# Main_Board_Germany_2016.net
KiCad netlist of a schematic drawn in EAGLE
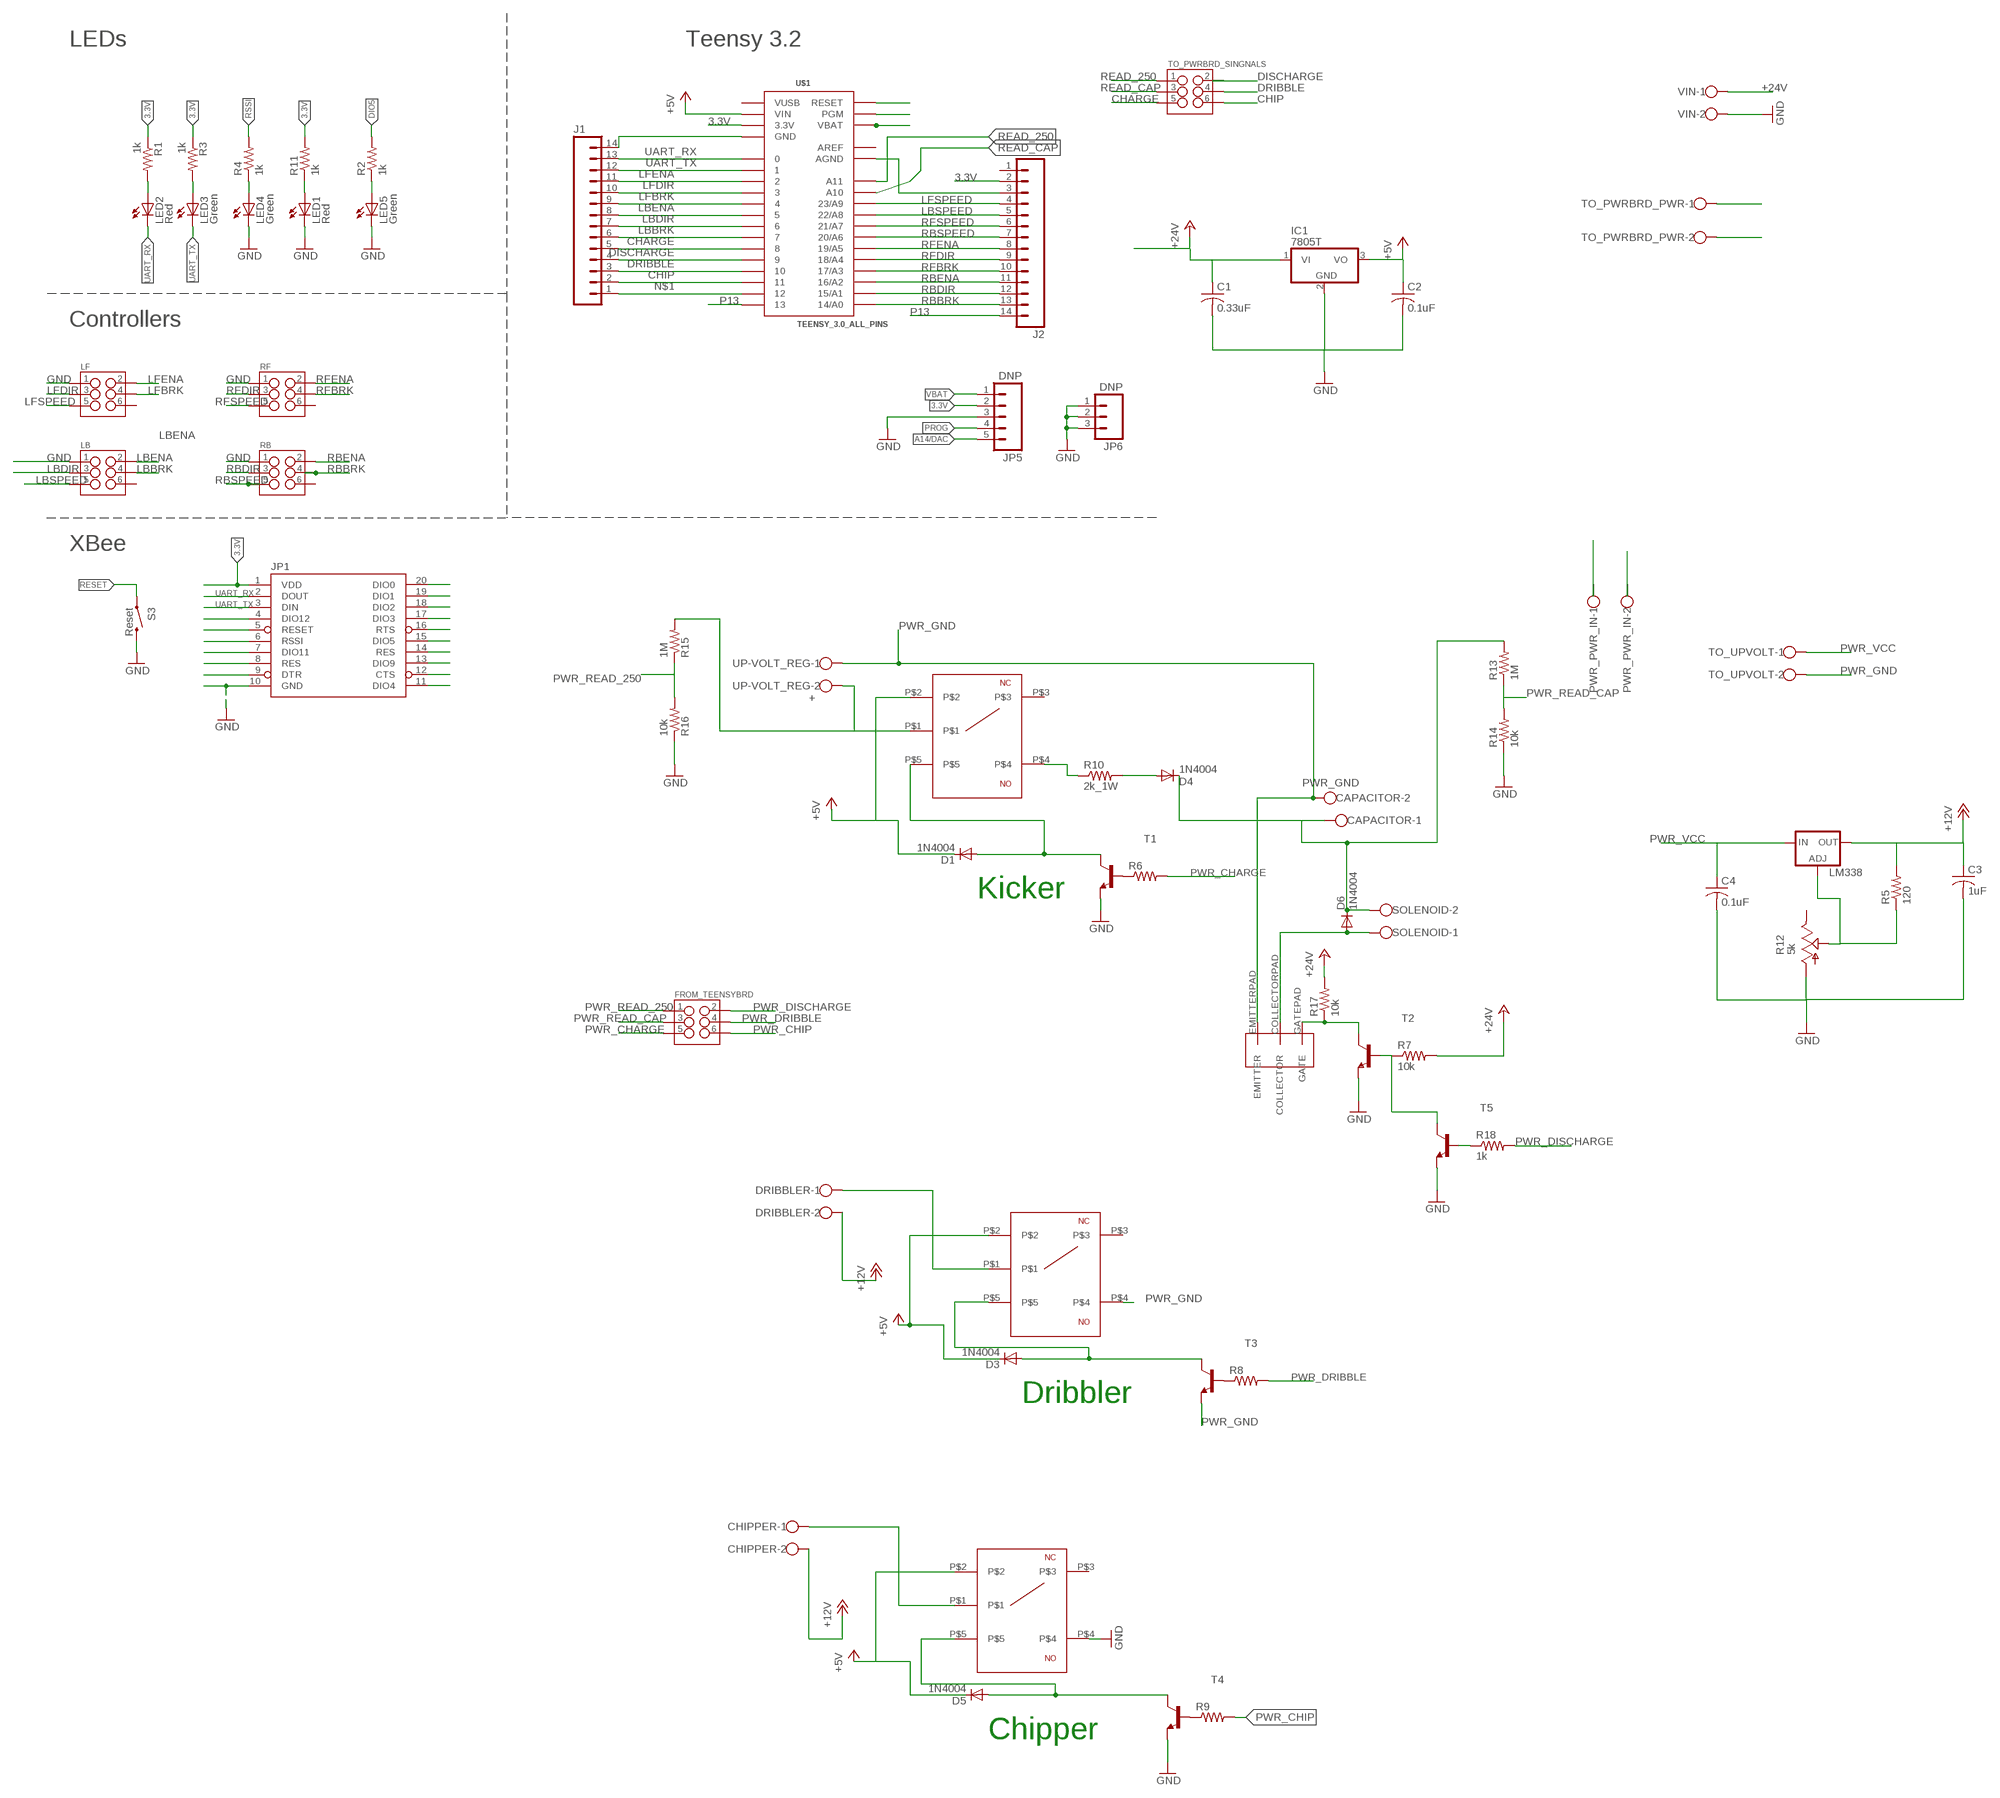
[diagram p0: schematic, sheet 1]

(export (version "E")
  (design (tool "Eeschema 10.0.6"))
  (components
    (comp (ref "C1")
      (value "0.33uF")
      (footprint "eagle-import:C0805")
      (libsource (lib "eagle-import") (part "C-USC0805"))
    )
    (comp (ref "C2")
      (value "0.1uF")
      (footprint "eagle-import:C0805")
      (libsource (lib "eagle-import") (part "C-USC0805"))
    )
    (comp (ref "C3")
      (value "1uF")
      (footprint "eagle-import:C0805")
      (libsource (lib "eagle-import") (part "C-USC0805"))
    )
    (comp (ref "C4")
      (value "0.1uF")
      (footprint "eagle-import:C0805")
      (libsource (lib "eagle-import") (part "C-USC0805"))
    )
    (comp (ref "CAPACITOR")
      (value "W237-102")
      (footprint "eagle-import:W237-102")
      (fields (field (name "MPN") "237-102"))
      (libsource (lib "eagle-import") (part "W237-102"))
    )
    (comp (ref "CHIPPER")
      (value "W237-102")
      (footprint "eagle-import:W237-102")
      (fields (field (name "MPN") "237-102"))
      (libsource (lib "eagle-import") (part "W237-102"))
    )
    (comp (ref "D1")
      (value "1N4004")
      (footprint "eagle-import:DO41-10")
      (libsource (lib "eagle-import") (part "1N4004"))
    )
    (comp (ref "D3")
      (value "1N4004")
      (footprint "eagle-import:DO41-10")
      (libsource (lib "eagle-import") (part "1N4004"))
    )
    (comp (ref "D4")
      (value "1N4004")
      (footprint "eagle-import:DO41-10")
      (libsource (lib "eagle-import") (part "1N4004"))
    )
    (comp (ref "D5")
      (value "1N4004")
      (footprint "eagle-import:DO41-10")
      (libsource (lib "eagle-import") (part "1N4004"))
    )
    (comp (ref "D6")
      (value "1N4004")
      (footprint "eagle-import:DO41-10")
      (libsource (lib "eagle-import") (part "1N4004"))
    )
    (comp (ref "DRIBBLER")
      (value "W237-102")
      (footprint "eagle-import:W237-102")
      (fields (field (name "MPN") "237-102"))
      (libsource (lib "eagle-import") (part "W237-102"))
    )
    (comp (ref "FROM_TEENSYBRD")
      (value "M03X2POGO_PINS")
      (footprint "eagle-import:2X3_POGO")
      (libsource (lib "eagle-import") (part "M03X2POGO_PINS"))
    )
    (comp (ref "IC1")
      (value "7805T")
      (footprint "eagle-import:TO220H")
      (libsource (lib "eagle-import") (part "78T05"))
    )
    (comp (ref "J1")
      (value "M14")
      (footprint "eagle-import:1X14")
      (libsource (lib "eagle-import") (part "M14"))
    )
    (comp (ref "J2")
      (value "M14")
      (footprint "eagle-import:1X14")
      (libsource (lib "eagle-import") (part "M14"))
    )
    (comp (ref "JP1")
      (value "XBEE-1B1")
      (footprint "eagle-import:XBEE-1")
      (libsource (lib "eagle-import") (part "XBEE-1B1"))
    )
    (comp (ref "JP5")
      (value "DNP")
      (footprint "eagle-import:1X05")
      (libsource (lib "eagle-import") (part "M05PTH"))
    )
    (comp (ref "JP6")
      (value "DNP")
      (footprint "eagle-import:1X03")
      (libsource (lib "eagle-import") (part "M03PTH"))
    )
    (comp (ref "LB")
      (value "M03X2POGO_PINS")
      (footprint "eagle-import:2X3_POGO")
      (libsource (lib "eagle-import") (part "M03X2POGO_PINS"))
    )
    (comp (ref "LED1")
      (value "Red")
      (footprint "eagle-import:LED-0603")
      (libsource (lib "eagle-import") (part "LED-RED0603"))
    )
    (comp (ref "LED2")
      (value "Red")
      (footprint "eagle-import:LED-0603")
      (libsource (lib "eagle-import") (part "LED-RED0603"))
    )
    (comp (ref "LED3")
      (value "Green")
      (footprint "eagle-import:LED-0603")
      (libsource (lib "eagle-import") (part "LED-GREEN0603"))
    )
    (comp (ref "LED4")
      (value "Green")
      (footprint "eagle-import:LED-0603")
      (libsource (lib "eagle-import") (part "LED-GREEN0603"))
    )
    (comp (ref "LED5")
      (value "Green")
      (footprint "eagle-import:LED-0603")
      (libsource (lib "eagle-import") (part "LED-GREEN0603"))
    )
    (comp (ref "LF")
      (value "M03X2POGO_PINS")
      (footprint "eagle-import:2X3_POGO")
      (libsource (lib "eagle-import") (part "M03X2POGO_PINS"))
    )
    (comp (ref "LM338")
      (value "LM317TL")
      (footprint "eagle-import:317TL")
      (libsource (lib "eagle-import") (part "LM317TL"))
    )
    (comp (ref "PWR_PWR_IN")
      (value "W237-102")
      (footprint "eagle-import:W237-102")
      (fields (field (name "MPN") "237-102"))
      (libsource (lib "eagle-import") (part "W237-102"))
    )
    (comp (ref "R1")
      (value "1k")
      (footprint "eagle-import:0603-RES")
      (libsource (lib "eagle-import") (part "1KOHM1/10W1%(0603)"))
    )
    (comp (ref "R2")
      (value "1k")
      (footprint "eagle-import:0603-RES")
      (libsource (lib "eagle-import") (part "1KOHM1/10W1%(0603)"))
    )
    (comp (ref "R3")
      (value "1k")
      (footprint "eagle-import:0603-RES")
      (libsource (lib "eagle-import") (part "1KOHM1/10W1%(0603)"))
    )
    (comp (ref "R4")
      (value "1k")
      (footprint "eagle-import:0603-RES")
      (libsource (lib "eagle-import") (part "1KOHM1/10W1%(0603)"))
    )
    (comp (ref "R5")
      (value "120")
      (footprint "eagle-import:M0805")
      (libsource (lib "eagle-import") (part "R-US_M0805"))
    )
    (comp (ref "R6")
      (value "R-US_0207/7")
      (footprint "eagle-import:0207_7")
      (libsource (lib "eagle-import") (part "R-US_0207/7"))
    )
    (comp (ref "R7")
      (value "10k")
      (footprint "eagle-import:0207_7")
      (libsource (lib "eagle-import") (part "R-US_0207/7"))
    )
    (comp (ref "R8")
      (value "R-US_0207/7")
      (footprint "eagle-import:0207_7")
      (libsource (lib "eagle-import") (part "R-US_0207/7"))
    )
    (comp (ref "R9")
      (value "R-US_0207/7")
      (footprint "eagle-import:0207_7")
      (libsource (lib "eagle-import") (part "R-US_0207/7"))
    )
    (comp (ref "R10")
      (value "2k_1W")
      (footprint "eagle-import:0309_12")
      (libsource (lib "eagle-import") (part "R-US_0309/12"))
    )
    (comp (ref "R11")
      (value "1k")
      (footprint "eagle-import:0603-RES")
      (libsource (lib "eagle-import") (part "1KOHM1/10W1%(0603)"))
    )
    (comp (ref "R12")
      (value "5k")
      (footprint "eagle-import:B25P")
      (libsource (lib "eagle-import") (part "TRIM_US-B25P"))
    )
    (comp (ref "R13")
      (value "1M")
      (footprint "eagle-import:M0805")
      (libsource (lib "eagle-import") (part "R-US_M0805"))
    )
    (comp (ref "R14")
      (value "10k")
      (footprint "eagle-import:M0805")
      (libsource (lib "eagle-import") (part "R-US_M0805"))
    )
    (comp (ref "R15")
      (value "1M")
      (footprint "eagle-import:M0805")
      (libsource (lib "eagle-import") (part "R-US_M0805"))
    )
    (comp (ref "R16")
      (value "10k")
      (footprint "eagle-import:M0805")
      (libsource (lib "eagle-import") (part "R-US_M0805"))
    )
    (comp (ref "R17")
      (value "10k")
      (footprint "eagle-import:0207_7")
      (libsource (lib "eagle-import") (part "R-US_0207/7"))
    )
    (comp (ref "R18")
      (value "1k")
      (footprint "eagle-import:0207_7")
      (libsource (lib "eagle-import") (part "R-US_0207/7"))
    )
    (comp (ref "RB")
      (value "M03X2POGO_PINS")
      (footprint "eagle-import:2X3_POGO")
      (libsource (lib "eagle-import") (part "M03X2POGO_PINS"))
    )
    (comp (ref "RF")
      (value "M03X2POGO_PINS")
      (footprint "eagle-import:2X3_POGO")
      (libsource (lib "eagle-import") (part "M03X2POGO_PINS"))
    )
    (comp (ref "S3")
      (value "Reset")
      (footprint "eagle-import:TACTILE-SWITCH-SMD")
      (libsource (lib "eagle-import") (part "SWITCH-MOMENTARY-2SMD"))
    )
    (comp (ref "SOLENOID")
      (value "W237-102")
      (footprint "eagle-import:W237-102")
      (fields (field (name "MPN") "237-102"))
      (libsource (lib "eagle-import") (part "W237-102"))
    )
    (comp (ref "T1")
      (value "2N3904-NPN-TO92-EBC")
      (footprint "eagle-import:TO92-EBC")
      (libsource (lib "eagle-import") (part "-NPN-TO92-EBC2N3904"))
    )
    (comp (ref "T2")
      (value "2N3904-NPN-TO92-EBC")
      (footprint "eagle-import:TO92-EBC")
      (libsource (lib "eagle-import") (part "-NPN-TO92-EBC2N3904"))
    )
    (comp (ref "T3")
      (value "2N3904-NPN-TO92-EBC")
      (footprint "eagle-import:TO92-EBC")
      (libsource (lib "eagle-import") (part "-NPN-TO92-EBC2N3904"))
    )
    (comp (ref "T4")
      (value "2N3904-NPN-TO92-EBC")
      (footprint "eagle-import:TO92-EBC")
      (libsource (lib "eagle-import") (part "-NPN-TO92-EBC2N3904"))
    )
    (comp (ref "T5")
      (value "2N3904-NPN-TO92-EBC")
      (footprint "eagle-import:TO92-EBC")
      (libsource (lib "eagle-import") (part "-NPN-TO92-EBC2N3904"))
    )
    (comp (ref "TO_PWRBRD_PWR")
      (value "W237-102")
      (footprint "eagle-import:W237-102")
      (fields (field (name "MPN") "237-102"))
      (libsource (lib "eagle-import") (part "W237-102"))
    )
    (comp (ref "TO_PWRBRD_SINGNALS")
      (value "M03X2POGO_PINS")
      (footprint "eagle-import:2X3_POGO")
      (libsource (lib "eagle-import") (part "M03X2POGO_PINS"))
    )
    (comp (ref "TO_UPVOLT")
      (value "W237-102")
      (footprint "eagle-import:W237-102")
      (fields (field (name "MPN") "237-102"))
      (libsource (lib "eagle-import") (part "W237-102"))
    )
    (comp (ref "U$1")
      (value "TEENSY_3.0_ALL_PINS")
      (footprint "eagle-import:TEENSY3-ALL_PINS")
      (libsource (lib "eagle-import") (part "TEENSY_3.0_ALL_PINS"))
    )
    (comp (ref "U$2")
      (value "APT75GN120LG")
      (footprint "eagle-import:TO-264")
      (libsource (lib "eagle-import") (part "APT75GN120LG"))
    )
    (comp (ref "U$3")
      (value "PANASONIC_JS1")
      (footprint "eagle-import:PANASONIC_JS1")
      (libsource (lib "eagle-import") (part "PANASONIC_JS1"))
    )
    (comp (ref "U$4")
      (value "PANASONIC_JS1")
      (footprint "eagle-import:PANASONIC_JS1")
      (libsource (lib "eagle-import") (part "PANASONIC_JS1"))
    )
    (comp (ref "U$5")
      (value "PANASONIC_JS1")
      (footprint "eagle-import:PANASONIC_JS1")
      (libsource (lib "eagle-import") (part "PANASONIC_JS1"))
    )
    (comp (ref "UP-VOLT_REG")
      (value "+")
      (footprint "eagle-import:W237-102")
      (fields (field (name "MPN") "237-102"))
      (libsource (lib "eagle-import") (part "W237-102"))
    )
    (comp (ref "VIN")
      (value "W237-102")
      (footprint "eagle-import:W237-102")
      (fields (field (name "MPN") "237-102"))
      (libsource (lib "eagle-import") (part "W237-102"))
    )
  )
  (nets
    (net (code "1") (name "+5V") (class "Default")
      (node (ref "C2") (pin "1") (pinfunction "1_1") (pintype "passive"))
      (node (ref "D1") (pin "C") (pinfunction "C_C") (pintype "passive"))
      (node (ref "D3") (pin "C") (pinfunction "C_C") (pintype "passive"))
      (node (ref "D5") (pin "C") (pinfunction "C_C") (pintype "passive"))
      (node (ref "IC1") (pin "3") (pinfunction "VO_3") (pintype "passive"))
      (node (ref "U$1") (pin "VIN") (pinfunction "VIN_VIN") (pintype "power_in"))
      (node (ref "U$3") (pin "P$2") (pinfunction "P$2_P$2") (pintype "bidirectional"))
      (node (ref "U$4") (pin "P$2") (pinfunction "P$2_P$2") (pintype "bidirectional"))
      (node (ref "U$5") (pin "P$2") (pinfunction "P$2_P$2") (pintype "bidirectional"))
    )
    (net (code "2") (name "+12V") (class "Default")
      (node (ref "C3") (pin "1") (pinfunction "1_1") (pintype "passive"))
      (node (ref "CHIPPER") (pin "2") (pinfunction "KL_2") (pintype "passive"))
      (node (ref "DRIBBLER") (pin "2") (pinfunction "KL_2") (pintype "passive"))
      (node (ref "LM338") (pin "2") (pinfunction "OUT_2") (pintype "passive"))
      (node (ref "R5") (pin "2") (pinfunction "2_2") (pintype "passive"))
    )
    (net (code "3") (name "+24V") (class "Default")
      (node (ref "C1") (pin "1") (pinfunction "1_1") (pintype "passive"))
      (node (ref "IC1") (pin "1") (pinfunction "VI_1") (pintype "input"))
      (node (ref "R17") (pin "2") (pinfunction "2_2") (pintype "passive"))
      (node (ref "R7") (pin "2") (pinfunction "2_2") (pintype "passive"))
      (node (ref "TO_PWRBRD_PWR") (pin "1") (pinfunction "KL_1") (pintype "passive"))
      (node (ref "VIN") (pin "1") (pinfunction "KL_1") (pintype "passive"))
    )
    (net (code "4") (name "/AREF") (class "Default")
      (node (ref "U$1") (pin "AREF") (pinfunction "AREF_AREF") (pintype "power_in"))
    )
    (net (code "5") (name "/CHARGE") (class "Default")
      (node (ref "J1") (pin "5") (pinfunction "5_5") (pintype "passive"))
      (node (ref "TO_PWRBRD_SINGNALS") (pin "P$5") (pinfunction "5_P$5") (pintype "bidirectional"))
      (node (ref "U$1") (pin "8") (pinfunction "8_8") (pintype "bidirectional"))
    )
    (net (code "6") (name "/CHIP") (class "Default")
      (node (ref "J1") (pin "2") (pinfunction "2_2") (pintype "passive"))
      (node (ref "TO_PWRBRD_SINGNALS") (pin "P$6") (pinfunction "6_P$6") (pintype "bidirectional"))
      (node (ref "U$1") (pin "11") (pinfunction "11_11") (pintype "bidirectional"))
    )
    (net (code "7") (name "/DISCHARGE") (class "Default")
      (node (ref "J1") (pin "4") (pinfunction "4_4") (pintype "passive"))
      (node (ref "U$1") (pin "9") (pinfunction "9_9") (pintype "bidirectional"))
    )
    (net (code "8") (name "/DRIBBLE") (class "Default")
      (node (ref "J1") (pin "3") (pinfunction "3_3") (pintype "passive"))
      (node (ref "TO_PWRBRD_SINGNALS") (pin "P$4") (pinfunction "4_P$4") (pintype "bidirectional"))
      (node (ref "U$1") (pin "10") (pinfunction "10_10") (pintype "bidirectional"))
    )
    (net (code "9") (name "/LBBRK") (class "Default")
      (node (ref "J1") (pin "6") (pinfunction "6_6") (pintype "passive"))
      (node (ref "LB") (pin "P$4") (pinfunction "4_P$4") (pintype "bidirectional"))
      (node (ref "U$1") (pin "7") (pinfunction "7_7") (pintype "bidirectional"))
    )
    (net (code "10") (name "/LBDIR") (class "Default")
      (node (ref "J1") (pin "7") (pinfunction "7_7") (pintype "passive"))
      (node (ref "LB") (pin "P$3") (pinfunction "3_P$3") (pintype "bidirectional"))
      (node (ref "U$1") (pin "6") (pinfunction "6_6") (pintype "bidirectional"))
    )
    (net (code "11") (name "/LBENA") (class "Default")
      (node (ref "J1") (pin "8") (pinfunction "8_8") (pintype "passive"))
      (node (ref "LB") (pin "P$2") (pinfunction "2_P$2") (pintype "bidirectional"))
      (node (ref "U$1") (pin "5") (pinfunction "5_5") (pintype "bidirectional"))
    )
    (net (code "12") (name "/LBSPEED") (class "Default")
      (node (ref "J2") (pin "5") (pinfunction "5_5") (pintype "passive"))
      (node (ref "LB") (pin "P$5") (pinfunction "5_P$5") (pintype "bidirectional"))
      (node (ref "U$1") (pin "22/A8") (pinfunction "22/A8_22/A8") (pintype "bidirectional"))
    )
    (net (code "13") (name "/LFBRK") (class "Default")
      (node (ref "J1") (pin "9") (pinfunction "9_9") (pintype "passive"))
      (node (ref "LF") (pin "P$4") (pinfunction "4_P$4") (pintype "bidirectional"))
      (node (ref "U$1") (pin "4") (pinfunction "4_4") (pintype "bidirectional"))
    )
    (net (code "14") (name "/LFDIR") (class "Default")
      (node (ref "J1") (pin "10") (pinfunction "10_10") (pintype "passive"))
      (node (ref "LF") (pin "P$3") (pinfunction "3_P$3") (pintype "bidirectional"))
      (node (ref "U$1") (pin "3") (pinfunction "3_3") (pintype "bidirectional"))
    )
    (net (code "15") (name "/LFENA") (class "Default")
      (node (ref "J1") (pin "11") (pinfunction "11_11") (pintype "passive"))
      (node (ref "LF") (pin "P$2") (pinfunction "2_P$2") (pintype "bidirectional"))
      (node (ref "U$1") (pin "2") (pinfunction "2_2") (pintype "bidirectional"))
    )
    (net (code "16") (name "/LFSPEED") (class "Default")
      (node (ref "J2") (pin "4") (pinfunction "4_4") (pintype "passive"))
      (node (ref "LF") (pin "P$5") (pinfunction "5_P$5") (pintype "bidirectional"))
      (node (ref "U$1") (pin "23/A9") (pinfunction "23/A9_23/A9") (pintype "bidirectional"))
    )
    (net (code "17") (name "/N$1") (class "Default")
      (node (ref "J1") (pin "1") (pinfunction "1_1") (pintype "passive"))
      (node (ref "U$1") (pin "12") (pinfunction "12_12") (pintype "bidirectional"))
    )
    (net (code "18") (name "/P13") (class "Default")
      (node (ref "J2") (pin "14") (pinfunction "14_14") (pintype "passive"))
      (node (ref "U$1") (pin "13") (pinfunction "13_13") (pintype "bidirectional"))
    )
    (net (code "19") (name "/PWR_CHARGE") (class "Default")
      (node (ref "FROM_TEENSYBRD") (pin "P$5") (pinfunction "5_P$5") (pintype "bidirectional"))
      (node (ref "R6") (pin "2") (pinfunction "2_2") (pintype "passive"))
    )
    (net (code "20") (name "/PWR_DISCHARGE") (class "Default")
      (node (ref "FROM_TEENSYBRD") (pin "P$2") (pinfunction "2_P$2") (pintype "bidirectional"))
      (node (ref "R18") (pin "2") (pinfunction "2_2") (pintype "passive"))
    )
    (net (code "21") (name "/PWR_DRIBBLE") (class "Default")
      (node (ref "FROM_TEENSYBRD") (pin "P$4") (pinfunction "4_P$4") (pintype "bidirectional"))
      (node (ref "R8") (pin "2") (pinfunction "2_2") (pintype "passive"))
    )
    (net (code "22") (name "/PWR_GND") (class "Default")
      (node (ref "CAPACITOR") (pin "2") (pinfunction "KL_2") (pintype "passive"))
      (node (ref "T3") (pin "E") (pinfunction "E_E") (pintype "passive"))
      (node (ref "TO_UPVOLT") (pin "2") (pinfunction "KL_2") (pintype "passive"))
      (node (ref "U$2") (pin "EMITTERPAD") (pinfunction "EMITTER_EMITTERPAD") (pintype "bidirectional"))
      (node (ref "U$4") (pin "P$4") (pinfunction "P$4_P$4") (pintype "bidirectional"))
      (node (ref "UP-VOLT_REG") (pin "1") (pinfunction "KL_1") (pintype "passive"))
    )
    (net (code "23") (name "/PWR_READ_250") (class "Default")
      (node (ref "FROM_TEENSYBRD") (pin "P$1") (pinfunction "1_P$1") (pintype "bidirectional"))
      (node (ref "R15") (pin "1") (pinfunction "1_1") (pintype "passive"))
      (node (ref "R16") (pin "2") (pinfunction "2_2") (pintype "passive"))
    )
    (net (code "24") (name "/PWR_READ_CAP") (class "Default")
      (node (ref "FROM_TEENSYBRD") (pin "P$3") (pinfunction "3_P$3") (pintype "bidirectional"))
      (node (ref "R13") (pin "1") (pinfunction "1_1") (pintype "passive"))
      (node (ref "R14") (pin "2") (pinfunction "2_2") (pintype "passive"))
    )
    (net (code "25") (name "/PWR_VCC") (class "Default")
      (node (ref "C4") (pin "1") (pinfunction "1_1") (pintype "passive"))
      (node (ref "LM338") (pin "3") (pinfunction "IN_3") (pintype "input"))
      (node (ref "TO_UPVOLT") (pin "1") (pinfunction "KL_1") (pintype "passive"))
    )
    (net (code "26") (name "/RBBRK") (class "Default")
      (node (ref "J2") (pin "13") (pinfunction "13_13") (pintype "passive"))
      (node (ref "RB") (pin "P$4") (pinfunction "4_P$4") (pintype "bidirectional"))
      (node (ref "U$1") (pin "14/A0") (pinfunction "14/A0_14/A0") (pintype "bidirectional"))
    )
    (net (code "27") (name "/RBDIR") (class "Default")
      (node (ref "J2") (pin "12") (pinfunction "12_12") (pintype "passive"))
      (node (ref "RB") (pin "P$3") (pinfunction "3_P$3") (pintype "bidirectional"))
      (node (ref "U$1") (pin "15/A1") (pinfunction "15/A1_15/A1") (pintype "bidirectional"))
    )
    (net (code "28") (name "/RBENA") (class "Default")
      (node (ref "J2") (pin "11") (pinfunction "11_11") (pintype "passive"))
      (node (ref "RB") (pin "P$2") (pinfunction "2_P$2") (pintype "bidirectional"))
      (node (ref "U$1") (pin "16/A2") (pinfunction "16/A2_16/A2") (pintype "bidirectional"))
    )
    (net (code "29") (name "/RBSPEED") (class "Default")
      (node (ref "J2") (pin "7") (pinfunction "7_7") (pintype "passive"))
      (node (ref "RB") (pin "P$5") (pinfunction "5_P$5") (pintype "bidirectional"))
      (node (ref "U$1") (pin "20/A6") (pinfunction "20/A6_20/A6") (pintype "bidirectional"))
    )
    (net (code "30") (name "/RFBRK") (class "Default")
      (node (ref "J2") (pin "10") (pinfunction "10_10") (pintype "passive"))
      (node (ref "RF") (pin "P$4") (pinfunction "4_P$4") (pintype "bidirectional"))
      (node (ref "U$1") (pin "17/A3") (pinfunction "17/A3_17/A3") (pintype "bidirectional"))
    )
    (net (code "31") (name "/RFDIR") (class "Default")
      (node (ref "J2") (pin "9") (pinfunction "9_9") (pintype "passive"))
      (node (ref "RF") (pin "P$3") (pinfunction "3_P$3") (pintype "bidirectional"))
      (node (ref "U$1") (pin "18/A4") (pinfunction "18/A4_18/A4") (pintype "bidirectional"))
    )
    (net (code "32") (name "/RFENA") (class "Default")
      (node (ref "J2") (pin "8") (pinfunction "8_8") (pintype "passive"))
      (node (ref "RF") (pin "P$2") (pinfunction "2_P$2") (pintype "bidirectional"))
      (node (ref "U$1") (pin "19/A5") (pinfunction "19/A5_19/A5") (pintype "bidirectional"))
    )
    (net (code "33") (name "/RFSPEED") (class "Default")
      (node (ref "J2") (pin "6") (pinfunction "6_6") (pintype "passive"))
      (node (ref "RF") (pin "P$5") (pinfunction "5_P$5") (pintype "bidirectional"))
      (node (ref "U$1") (pin "21/A7") (pinfunction "21/A7_21/A7") (pintype "bidirectional"))
    )
    (net (code "34") (name "/VUSB") (class "Default")
      (node (ref "U$1") (pin "VUSB") (pinfunction "VUSB_VUSB") (pintype "power_in"))
    )
    (net (code "35") (name "3.3V") (class "Default")
      (node (ref "J2") (pin "2") (pinfunction "2_2") (pintype "passive"))
      (node (ref "JP1") (pin "1") (pinfunction "VDD_1") (pintype "power_in"))
      (node (ref "JP5") (pin "2") (pinfunction "2_2") (pintype "passive"))
      (node (ref "R1") (pin "1") (pinfunction "1_1") (pintype "passive"))
      (node (ref "R11") (pin "2") (pinfunction "2_2") (pintype "passive"))
      (node (ref "R3") (pin "1") (pinfunction "1_1") (pintype "passive"))
      (node (ref "U$1") (pin "3.3V") (pinfunction "3.3V_3.3V") (pintype "power_in"))
      (node (ref "U$1") (pin "3.3V1") (pinfunction "3.3V_3.3V1") (pintype "power_in"))
    )
    (net (code "36") (name "A14{slash}DAC") (class "Default")
      (node (ref "JP5") (pin "5") (pinfunction "5_5") (pintype "passive"))
      (node (ref "U$1") (pin "RESET/DAC") (pinfunction "RESET_RESET/DAC") (pintype "bidirectional"))
    )
    (net (code "37") (name "DIO5") (class "Default")
      (node (ref "JP1") (pin "15") (pinfunction "DIO5_15") (pintype "bidirectional"))
      (node (ref "R2") (pin "2") (pinfunction "2_2") (pintype "passive"))
    )
    (net (code "38") (name "GND") (class "Default")
      (node (ref "C1") (pin "2") (pinfunction "2_2") (pintype "passive"))
      (node (ref "C2") (pin "2") (pinfunction "2_2") (pintype "passive"))
      (node (ref "C3") (pin "2") (pinfunction "2_2") (pintype "passive"))
      (node (ref "C4") (pin "2") (pinfunction "2_2") (pintype "passive"))
      (node (ref "IC1") (pin "2") (pinfunction "GND_2") (pintype "passive"))
      (node (ref "J1") (pin "14") (pinfunction "14_14") (pintype "passive"))
      (node (ref "JP1") (pin "10") (pinfunction "GND_10") (pintype "power_in"))
      (node (ref "JP5") (pin "3") (pinfunction "3_3") (pintype "passive"))
      (node (ref "JP6") (pin "1") (pinfunction "1_1") (pintype "passive"))
      (node (ref "JP6") (pin "2") (pinfunction "2_2") (pintype "passive"))
      (node (ref "JP6") (pin "3") (pinfunction "3_3") (pintype "passive"))
      (node (ref "LB") (pin "P$1") (pinfunction "1_P$1") (pintype "bidirectional"))
      (node (ref "LED1") (pin "C") (pinfunction "C_C") (pintype "passive"))
      (node (ref "LED4") (pin "C") (pinfunction "C_C") (pintype "passive"))
      (node (ref "LED5") (pin "C") (pinfunction "C_C") (pintype "passive"))
      (node (ref "LF") (pin "P$1") (pinfunction "1_P$1") (pintype "bidirectional"))
      (node (ref "R12") (pin "A") (pinfunction "A_A") (pintype "passive"))
      (node (ref "R14") (pin "1") (pinfunction "1_1") (pintype "passive"))
      (node (ref "R16") (pin "1") (pinfunction "1_1") (pintype "passive"))
      (node (ref "RB") (pin "P$1") (pinfunction "1_P$1") (pintype "bidirectional"))
      (node (ref "RF") (pin "P$1") (pinfunction "1_P$1") (pintype "bidirectional"))
      (node (ref "S3") (pin "3") (pinfunction "2_3") (pintype "passive"))
      (node (ref "T1") (pin "E") (pinfunction "E_E") (pintype "passive"))
      (node (ref "T2") (pin "E") (pinfunction "E_E") (pintype "passive"))
      (node (ref "T4") (pin "E") (pinfunction "E_E") (pintype "passive"))
      (node (ref "T5") (pin "E") (pinfunction "E_E") (pintype "passive"))
      (node (ref "TO_PWRBRD_PWR") (pin "2") (pinfunction "KL_2") (pintype "passive"))
      (node (ref "U$1") (pin "GND") (pinfunction "GND_GND") (pintype "power_in"))
      (node (ref "U$1") (pin "GND1") (pinfunction "GND_GND1") (pintype "power_in"))
      (node (ref "U$5") (pin "P$4") (pinfunction "P$4_P$4") (pintype "bidirectional"))
      (node (ref "VIN") (pin "2") (pinfunction "KL_2") (pintype "passive"))
    )
    (net (code "39") (name "Net-(CAPACITORA-KL)") (class "Default")
      (node (ref "CAPACITOR") (pin "1") (pinfunction "KL_1") (pintype "passive"))
      (node (ref "D4") (pin "C") (pinfunction "C_C") (pintype "passive"))
      (node (ref "D6") (pin "C") (pinfunction "C_C") (pintype "passive"))
      (node (ref "R13") (pin "2") (pinfunction "2_2") (pintype "passive"))
      (node (ref "SOLENOID") (pin "2") (pinfunction "KL_2") (pintype "passive"))
    )
    (net (code "40") (name "Net-(CHIPPERA-KL)") (class "Default")
      (node (ref "CHIPPER") (pin "1") (pinfunction "KL_1") (pintype "passive"))
      (node (ref "U$5") (pin "P$1") (pinfunction "P$1_P$1") (pintype "bidirectional"))
    )
    (net (code "41") (name "Net-(D1-PadA)") (class "Default")
      (node (ref "D1") (pin "A") (pinfunction "A_A") (pintype "passive"))
      (node (ref "T1") (pin "C") (pinfunction "C_C") (pintype "passive"))
      (node (ref "U$3") (pin "P$5") (pinfunction "P$5_P$5") (pintype "bidirectional"))
    )
    (net (code "42") (name "Net-(D3-PadA)") (class "Default")
      (node (ref "D3") (pin "A") (pinfunction "A_A") (pintype "passive"))
      (node (ref "T3") (pin "C") (pinfunction "C_C") (pintype "passive"))
      (node (ref "U$4") (pin "P$5") (pinfunction "P$5_P$5") (pintype "bidirectional"))
    )
    (net (code "43") (name "Net-(D4-PadA)") (class "Default")
      (node (ref "D4") (pin "A") (pinfunction "A_A") (pintype "passive"))
      (node (ref "R10") (pin "2") (pinfunction "2_2") (pintype "passive"))
    )
    (net (code "44") (name "Net-(D5-PadA)") (class "Default")
      (node (ref "D5") (pin "A") (pinfunction "A_A") (pintype "passive"))
      (node (ref "T4") (pin "C") (pinfunction "C_C") (pintype "passive"))
      (node (ref "U$5") (pin "P$5") (pinfunction "P$5_P$5") (pintype "bidirectional"))
    )
    (net (code "45") (name "Net-(DRIBBLERA-KL)") (class "Default")
      (node (ref "DRIBBLER") (pin "1") (pinfunction "KL_1") (pintype "passive"))
      (node (ref "U$4") (pin "P$1") (pinfunction "P$1_P$1") (pintype "bidirectional"))
    )
    (net (code "46") (name "Net-(J2-Pad3)") (class "Default")
      (node (ref "J2") (pin "3") (pinfunction "3_3") (pintype "passive"))
      (node (ref "U$1") (pin "AGND") (pinfunction "AGND_AGND") (pintype "power_in"))
    )
    (net (code "47") (name "Net-(LED1-PadA)") (class "Default")
      (node (ref "LED1") (pin "A") (pinfunction "A_A") (pintype "passive"))
      (node (ref "R11") (pin "1") (pinfunction "1_1") (pintype "passive"))
    )
    (net (code "48") (name "Net-(LED2-PadA)") (class "Default")
      (node (ref "LED2") (pin "A") (pinfunction "A_A") (pintype "passive"))
      (node (ref "R1") (pin "2") (pinfunction "2_2") (pintype "passive"))
    )
    (net (code "49") (name "Net-(LED3-PadA)") (class "Default")
      (node (ref "LED3") (pin "A") (pinfunction "A_A") (pintype "passive"))
      (node (ref "R3") (pin "2") (pinfunction "2_2") (pintype "passive"))
    )
    (net (code "50") (name "Net-(LED4-PadA)") (class "Default")
      (node (ref "LED4") (pin "A") (pinfunction "A_A") (pintype "passive"))
      (node (ref "R4") (pin "1") (pinfunction "1_1") (pintype "passive"))
    )
    (net (code "51") (name "Net-(LED5-PadA)") (class "Default")
      (node (ref "LED5") (pin "A") (pinfunction "A_A") (pintype "passive"))
      (node (ref "R2") (pin "1") (pinfunction "1_1") (pintype "passive"))
    )
    (net (code "52") (name "Net-(LM338-ADJ)") (class "Default")
      (node (ref "LM338") (pin "1") (pinfunction "ADJ_1") (pintype "input"))
      (node (ref "R12") (pin "S") (pinfunction "S_S") (pintype "passive"))
      (node (ref "R5") (pin "1") (pinfunction "1_1") (pintype "passive"))
    )
    (net (code "53") (name "Net-(R6-Pad1)") (class "Default")
      (node (ref "R6") (pin "1") (pinfunction "1_1") (pintype "passive"))
      (node (ref "T1") (pin "B") (pinfunction "B_B") (pintype "passive"))
    )
    (net (code "54") (name "Net-(R7-Pad1)") (class "Default")
      (node (ref "R7") (pin "1") (pinfunction "1_1") (pintype "passive"))
      (node (ref "T2") (pin "B") (pinfunction "B_B") (pintype "passive"))
      (node (ref "T5") (pin "C") (pinfunction "C_C") (pintype "passive"))
    )
    (net (code "55") (name "Net-(R8-Pad1)") (class "Default")
      (node (ref "R8") (pin "1") (pinfunction "1_1") (pintype "passive"))
      (node (ref "T3") (pin "B") (pinfunction "B_B") (pintype "passive"))
    )
    (net (code "56") (name "Net-(R9-Pad1)") (class "Default")
      (node (ref "R9") (pin "1") (pinfunction "1_1") (pintype "passive"))
      (node (ref "T4") (pin "B") (pinfunction "B_B") (pintype "passive"))
    )
    (net (code "57") (name "Net-(R10-Pad1)") (class "Default")
      (node (ref "R10") (pin "1") (pinfunction "1_1") (pintype "passive"))
      (node (ref "U$3") (pin "P$4") (pinfunction "P$4_P$4") (pintype "bidirectional"))
    )
    (net (code "58") (name "Net-(R18-Pad1)") (class "Default")
      (node (ref "R18") (pin "1") (pinfunction "1_1") (pintype "passive"))
      (node (ref "T5") (pin "B") (pinfunction "B_B") (pintype "passive"))
    )
    (net (code "59") (name "Net-(SOLENOIDA-KL)") (class "Default")
      (node (ref "D6") (pin "A") (pinfunction "A_A") (pintype "passive"))
      (node (ref "SOLENOID") (pin "1") (pinfunction "KL_1") (pintype "passive"))
      (node (ref "U$2") (pin "COLLECTORPAD") (pinfunction "COLLECTOR_COLLECTORPAD") (pintype "bidirectional"))
    )
    (net (code "60") (name "Net-(U$2-GATE)") (class "Default")
      (node (ref "R17") (pin "1") (pinfunction "1_1") (pintype "passive"))
      (node (ref "T2") (pin "C") (pinfunction "C_C") (pintype "passive"))
      (node (ref "U$2") (pin "GATEPAD") (pinfunction "GATE_GATEPAD") (pintype "bidirectional"))
    )
    (net (code "61") (name "Net-(UP-VOLT_REGB-KL)") (class "Default")
      (node (ref "R15") (pin "2") (pinfunction "2_2") (pintype "passive"))
      (node (ref "U$3") (pin "P$1") (pinfunction "P$1_P$1") (pintype "bidirectional"))
      (node (ref "UP-VOLT_REG") (pin "2") (pinfunction "KL_2") (pintype "passive"))
    )
    (net (code "62") (name "PROG") (class "Default")
      (node (ref "JP5") (pin "4") (pinfunction "4_4") (pintype "passive"))
      (node (ref "U$1") (pin "PGM") (pinfunction "PGM_PGM") (pintype "bidirectional"))
    )
    (net (code "63") (name "PWR_CHIP") (class "Default")
      (node (ref "FROM_TEENSYBRD") (pin "P$6") (pinfunction "6_P$6") (pintype "bidirectional"))
      (node (ref "R9") (pin "2") (pinfunction "2_2") (pintype "passive"))
    )
    (net (code "64") (name "READ_250") (class "Default")
      (node (ref "TO_PWRBRD_SINGNALS") (pin "P$1") (pinfunction "1_P$1") (pintype "bidirectional"))
      (node (ref "U$1") (pin "A11") (pinfunction "A11_A11") (pintype "bidirectional"))
    )
    (net (code "65") (name "READ_CAP") (class "Default")
      (node (ref "TO_PWRBRD_SINGNALS") (pin "P$3") (pinfunction "3_P$3") (pintype "bidirectional"))
      (node (ref "U$1") (pin "A10") (pinfunction "A10_A10") (pintype "bidirectional"))
    )
    (net (code "66") (name "RESET") (class "Default")
      (node (ref "JP1") (pin "5") (pinfunction "RESET_5") (pintype "input"))
      (node (ref "S3") (pin "1") (pinfunction "1_1") (pintype "passive"))
    )
    (net (code "67") (name "RSSI") (class "Default")
      (node (ref "JP1") (pin "6") (pinfunction "RSSI_6") (pintype "bidirectional"))
      (node (ref "R4") (pin "2") (pinfunction "2_2") (pintype "passive"))
    )
    (net (code "68") (name "UART_RX") (class "Default")
      (node (ref "J1") (pin "13") (pinfunction "13_13") (pintype "passive"))
      (node (ref "JP1") (pin "2") (pinfunction "DOUT_2") (pintype "output"))
      (node (ref "LED2") (pin "C") (pinfunction "C_C") (pintype "passive"))
      (node (ref "U$1") (pin "0") (pinfunction "0_0") (pintype "bidirectional"))
    )
    (net (code "69") (name "UART_TX") (class "Default")
      (node (ref "J1") (pin "12") (pinfunction "12_12") (pintype "passive"))
      (node (ref "JP1") (pin "3") (pinfunction "DIN_3") (pintype "input"))
      (node (ref "LED3") (pin "C") (pinfunction "C_C") (pintype "passive"))
      (node (ref "U$1") (pin "1") (pinfunction "1_1") (pintype "bidirectional"))
    )
    (net (code "70") (name "VBAT") (class "Default")
      (node (ref "JP5") (pin "1") (pinfunction "1_1") (pintype "passive"))
      (node (ref "U$1") (pin "VBAT") (pinfunction "VBAT_VBAT") (pintype "power_in"))
    )
    (net (code "71") (name "unconnected-(J2-Pad1)") (class "Default")
      (node (ref "J2") (pin "1") (pinfunction "1_1") (pintype "passive"))
    )
    (net (code "72") (name "unconnected-(JP1-CTS-Pad12)") (class "Default")
      (node (ref "JP1") (pin "12") (pinfunction "CTS_12") (pintype "output"))
    )
    (net (code "73") (name "unconnected-(JP1-DIO0-Pad20)") (class "Default")
      (node (ref "JP1") (pin "20") (pinfunction "DIO0_20") (pintype "bidirectional"))
    )
    (net (code "74") (name "unconnected-(JP1-DIO1-Pad19)") (class "Default")
      (node (ref "JP1") (pin "19") (pinfunction "DIO1_19") (pintype "bidirectional"))
    )
    (net (code "75") (name "unconnected-(JP1-DIO2-Pad18)") (class "Default")
      (node (ref "JP1") (pin "18") (pinfunction "DIO2_18") (pintype "bidirectional"))
    )
    (net (code "76") (name "unconnected-(JP1-DIO3-Pad17)") (class "Default")
      (node (ref "JP1") (pin "17") (pinfunction "DIO3_17") (pintype "bidirectional"))
    )
    (net (code "77") (name "unconnected-(JP1-DIO4-Pad11)") (class "Default")
      (node (ref "JP1") (pin "11") (pinfunction "DIO4_11") (pintype "bidirectional"))
    )
    (net (code "78") (name "unconnected-(JP1-DIO9-Pad13)") (class "Default")
      (node (ref "JP1") (pin "13") (pinfunction "DIO9_13") (pintype "bidirectional"))
    )
    (net (code "79") (name "unconnected-(JP1-DIO11-Pad7)") (class "Default")
      (node (ref "JP1") (pin "7") (pinfunction "DIO11_7") (pintype "bidirectional"))
    )
    (net (code "80") (name "unconnected-(JP1-DIO12-Pad4)") (class "Default")
      (node (ref "JP1") (pin "4") (pinfunction "DIO12_4") (pintype "bidirectional"))
    )
    (net (code "81") (name "unconnected-(JP1-DTR-Pad9)") (class "Default")
      (node (ref "JP1") (pin "9") (pinfunction "DTR_9") (pintype "bidirectional"))
    )
    (net (code "82") (name "unconnected-(JP1-RES-Pad8)") (class "Default")
      (node (ref "JP1") (pin "8") (pinfunction "RES_8") (pintype "bidirectional"))
    )
    (net (code "83") (name "unconnected-(JP1-RES-Pad14)") (class "Default")
      (node (ref "JP1") (pin "14") (pinfunction "RES_14") (pintype "bidirectional"))
    )
    (net (code "84") (name "unconnected-(JP1-RTS-Pad16)") (class "Default")
      (node (ref "JP1") (pin "16") (pinfunction "RTS_16") (pintype "input"))
    )
    (net (code "85") (name "unconnected-(LB-6-PadP$6)") (class "Default")
      (node (ref "LB") (pin "P$6") (pinfunction "6_P$6") (pintype "bidirectional"))
    )
    (net (code "86") (name "unconnected-(LF-6-PadP$6)") (class "Default")
      (node (ref "LF") (pin "P$6") (pinfunction "6_P$6") (pintype "bidirectional"))
    )
    (net (code "87") (name "unconnected-(PWR_PWR_INA-KL-Pad1)") (class "Default")
      (node (ref "PWR_PWR_IN") (pin "1") (pinfunction "KL_1") (pintype "passive"))
    )
    (net (code "88") (name "unconnected-(PWR_PWR_INB-KL-Pad2)") (class "Default")
      (node (ref "PWR_PWR_IN") (pin "2") (pinfunction "KL_2") (pintype "passive"))
    )
    (net (code "89") (name "unconnected-(R12-PadE)") (class "Default")
      (node (ref "R12") (pin "E") (pinfunction "E_E") (pintype "passive"))
    )
    (net (code "90") (name "unconnected-(RB-6-PadP$6)") (class "Default")
      (node (ref "RB") (pin "P$6") (pinfunction "6_P$6") (pintype "bidirectional"))
    )
    (net (code "91") (name "unconnected-(RF-6-PadP$6)") (class "Default")
      (node (ref "RF") (pin "P$6") (pinfunction "6_P$6") (pintype "bidirectional"))
    )
    (net (code "92") (name "unconnected-(TO_PWRBRD_SINGNALS-2-PadP$2)") (class "Default")
      (node (ref "TO_PWRBRD_SINGNALS") (pin "P$2") (pinfunction "2_P$2") (pintype "bidirectional"))
    )
    (net (code "93") (name "unconnected-(U$3-PadP$3)") (class "Default")
      (node (ref "U$3") (pin "P$3") (pinfunction "P$3_P$3") (pintype "bidirectional"))
    )
    (net (code "94") (name "unconnected-(U$4-PadP$3)") (class "Default")
      (node (ref "U$4") (pin "P$3") (pinfunction "P$3_P$3") (pintype "bidirectional"))
    )
    (net (code "95") (name "unconnected-(U$5-PadP$3)") (class "Default")
      (node (ref "U$5") (pin "P$3") (pinfunction "P$3_P$3") (pintype "bidirectional"))
    )
  )
)
